# benchPS.net
KiCad netlist of a schematic drawn in EAGLE
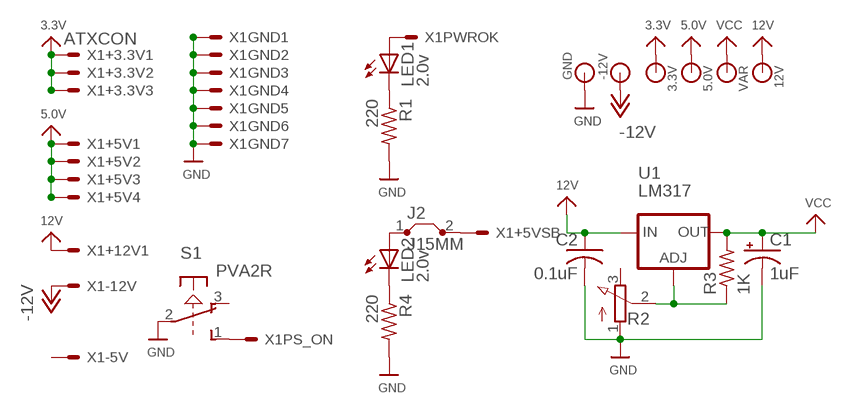
[diagram p0: schematic, sheet 1]

(export (version "E")
  (design (tool "Eeschema 10.0.6"))
  (components
    (comp (ref "-12V")
      (value "BANANA_CONN")
      (footprint "eagle-import:BANANA_CONN")
      (libsource (lib "eagle-import") (part "BANANA_CONN"))
    )
    (comp (ref "3.3V")
      (value "BANANA_CONN")
      (footprint "eagle-import:BANANA_CONN")
      (libsource (lib "eagle-import") (part "BANANA_CONN"))
    )
    (comp (ref "5.0V")
      (value "BANANA_CONN")
      (footprint "eagle-import:BANANA_CONN")
      (libsource (lib "eagle-import") (part "BANANA_CONN"))
    )
    (comp (ref "12V")
      (value "BANANA_CONN")
      (footprint "eagle-import:BANANA_CONN")
      (libsource (lib "eagle-import") (part "BANANA_CONN"))
    )
    (comp (ref "C1")
      (value "1uF")
      (footprint "eagle-import:E3,5-8")
      (libsource (lib "eagle-import") (part "CPOL-USE3.5-8"))
    )
    (comp (ref "C2")
      (value "0.1uF")
      (footprint "eagle-import:C050-025X075")
      (libsource (lib "eagle-import") (part "C-US050-025X075"))
    )
    (comp (ref "GND")
      (value "BANANA_CONN")
      (footprint "eagle-import:BANANA_CONN")
      (libsource (lib "eagle-import") (part "BANANA_CONN"))
    )
    (comp (ref "J2")
      (value "J15MM")
      (footprint "eagle-import:15")
      (libsource (lib "eagle-import") (part "J15MM"))
    )
    (comp (ref "LED1")
      (value "2.0v")
      (footprint "eagle-import:LED3MM")
      (libsource (lib "eagle-import") (part "LED3MM"))
    )
    (comp (ref "LED2")
      (value "2.0v")
      (footprint "eagle-import:LED3MM")
      (libsource (lib "eagle-import") (part "LED3MM"))
    )
    (comp (ref "R1")
      (value "220")
      (footprint "eagle-import:0204_7")
      (libsource (lib "eagle-import") (part "R-US_0204/7"))
    )
    (comp (ref "R2")
      (value "3RP/1610N")
      (footprint "eagle-import:3RP_1610N")
      (libsource (lib "eagle-import") (part "3RP/1610N"))
    )
    (comp (ref "R3")
      (value "1K")
      (footprint "eagle-import:0204_7")
      (libsource (lib "eagle-import") (part "R-US_0204/7"))
    )
    (comp (ref "R4")
      (value "220")
      (footprint "eagle-import:0204_7")
      (libsource (lib "eagle-import") (part "R-US_0204/7"))
    )
    (comp (ref "S1")
      (value "PVA2R")
      (footprint "eagle-import:PVA2R")
      (libsource (lib "eagle-import") (part "PVA2R"))
    )
    (comp (ref "U1")
      (value "LM317")
      (footprint "eagle-import:TO220-ADJ")
      (libsource (lib "eagle-import") (part "V_REG_317SINK"))
    )
    (comp (ref "VAR")
      (value "BANANA_CONN")
      (footprint "eagle-import:BANANA_CONN")
      (libsource (lib "eagle-import") (part "BANANA_CONN"))
    )
    (comp (ref "X1")
      (value "ATXCON")
      (footprint "eagle-import:5566-20")
      (libsource (lib "eagle-import") (part "ATXCON"))
    )
  )
  (nets
    (net (code "1") (name "-12V") (class "Default")
      (node (ref "-12V") (pin "P$1") (pinfunction "1_P$1") (pintype "passive"))
      (node (ref "X1") (pin "12") (pinfunction "S_12") (pintype "passive"))
    )
    (net (code "2") (name "3.3V") (class "Default")
      (node (ref "3.3V") (pin "P$1") (pinfunction "1_P$1") (pintype "passive"))
      (node (ref "X1") (pin "1") (pinfunction "S_1") (pintype "passive"))
      (node (ref "X1") (pin "11") (pinfunction "S_11") (pintype "passive"))
      (node (ref "X1") (pin "2") (pinfunction "S_2") (pintype "passive"))
    )
    (net (code "3") (name "5.0V") (class "Default")
      (node (ref "5.0V") (pin "P$1") (pinfunction "1_P$1") (pintype "passive"))
      (node (ref "X1") (pin "19") (pinfunction "S_19") (pintype "passive"))
      (node (ref "X1") (pin "20") (pinfunction "S_20") (pintype "passive"))
      (node (ref "X1") (pin "4") (pinfunction "S_4") (pintype "passive"))
      (node (ref "X1") (pin "6") (pinfunction "S_6") (pintype "passive"))
    )
    (net (code "4") (name "12V") (class "Default")
      (node (ref "12V") (pin "P$1") (pinfunction "1_P$1") (pintype "passive"))
      (node (ref "C2") (pin "1") (pinfunction "1_1") (pintype "passive"))
      (node (ref "U1") (pin "IN") (pinfunction "IN_IN") (pintype "input"))
      (node (ref "X1") (pin "10") (pinfunction "S_10") (pintype "passive"))
    )
    (net (code "5") (name "GND") (class "Default")
      (node (ref "C1") (pin "-") (pinfunction "-_-") (pintype "passive"))
      (node (ref "C2") (pin "2") (pinfunction "2_2") (pintype "passive"))
      (node (ref "GND") (pin "P$1") (pinfunction "1_P$1") (pintype "passive"))
      (node (ref "R1") (pin "2") (pinfunction "2_2") (pintype "passive"))
      (node (ref "R2") (pin "1") (pinfunction "A_1") (pintype "passive"))
      (node (ref "R4") (pin "2") (pinfunction "2_2") (pintype "passive"))
      (node (ref "S1") (pin "2") (pinfunction "P_2") (pintype "passive"))
      (node (ref "X1") (pin "13") (pinfunction "S_13") (pintype "passive"))
      (node (ref "X1") (pin "15") (pinfunction "S_15") (pintype "passive"))
      (node (ref "X1") (pin "16") (pinfunction "S_16") (pintype "passive"))
      (node (ref "X1") (pin "17") (pinfunction "S_17") (pintype "passive"))
      (node (ref "X1") (pin "3") (pinfunction "S_3") (pintype "passive"))
      (node (ref "X1") (pin "5") (pinfunction "S_5") (pintype "passive"))
      (node (ref "X1") (pin "7") (pinfunction "S_7") (pintype "passive"))
    )
    (net (code "6") (name "Net-(J2-Pad1)") (class "Default")
      (node (ref "J2") (pin "1") (pinfunction "1_1") (pintype "passive"))
      (node (ref "LED2") (pin "A") (pinfunction "A_A") (pintype "passive"))
    )
    (net (code "7") (name "Net-(LED1-C)") (class "Default")
      (node (ref "LED1") (pin "K") (pinfunction "C_K") (pintype "passive"))
      (node (ref "R1") (pin "1") (pinfunction "1_1") (pintype "passive"))
    )
    (net (code "8") (name "Net-(LED2-C)") (class "Default")
      (node (ref "LED2") (pin "K") (pinfunction "C_K") (pintype "passive"))
      (node (ref "R4") (pin "1") (pinfunction "1_1") (pintype "passive"))
    )
    (net (code "9") (name "Net-(R2-S)") (class "Default")
      (node (ref "R2") (pin "2") (pinfunction "S_2") (pintype "passive"))
      (node (ref "R3") (pin "1") (pinfunction "1_1") (pintype "passive"))
      (node (ref "U1") (pin "ADJ") (pinfunction "ADJ_ADJ") (pintype "input"))
    )
    (net (code "10") (name "Net-(S1A-S)") (class "Default")
      (node (ref "S1") (pin "1") (pinfunction "S_1") (pintype "passive"))
      (node (ref "X1") (pin "14") (pinfunction "S_14") (pintype "passive"))
    )
    (net (code "11") (name "Net-(X1I-S)") (class "Default")
      (node (ref "J2") (pin "2") (pinfunction "2_2") (pintype "passive"))
      (node (ref "X1") (pin "9") (pinfunction "S_9") (pintype "passive"))
    )
    (net (code "12") (name "Net-(X1T-S)") (class "Default")
      (node (ref "LED1") (pin "A") (pinfunction "A_A") (pintype "passive"))
      (node (ref "X1") (pin "8") (pinfunction "S_8") (pintype "passive"))
    )
    (net (code "13") (name "VCC") (class "Default")
      (node (ref "C1") (pin "+") (pinfunction "+_+") (pintype "passive"))
      (node (ref "R3") (pin "2") (pinfunction "2_2") (pintype "passive"))
      (node (ref "U1") (pin "OUT") (pinfunction "OUT_OUT") (pintype "output"))
      (node (ref "VAR") (pin "P$1") (pinfunction "1_P$1") (pintype "passive"))
    )
    (net (code "14") (name "unconnected-(R2-E-Pad3)") (class "Default")
      (node (ref "R2") (pin "3") (pinfunction "E_3") (pintype "passive"))
    )
    (net (code "15") (name "unconnected-(S1A-O-Pad3)") (class "Default")
      (node (ref "S1") (pin "3") (pinfunction "O_3") (pintype "passive"))
    )
    (net (code "16") (name "unconnected-(X1K-S-Pad18)") (class "Default")
      (node (ref "X1") (pin "18") (pinfunction "S_18") (pintype "passive"))
    )
  )
)
